# Page-10.net
KiCad netlist of a schematic drawn in Altium Designer
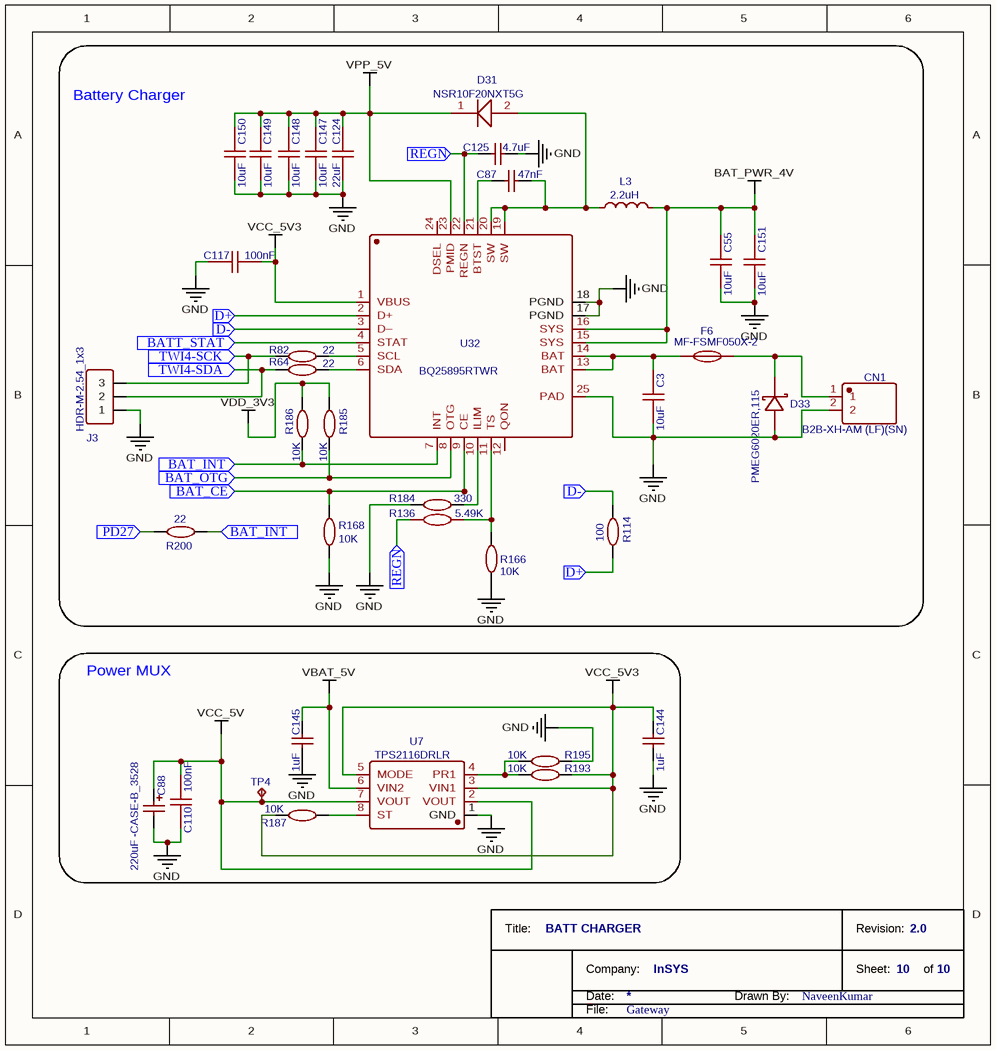
[diagram p0: Page-10.schdoc]

(export (version "E")
  (design (tool "Eeschema 10.0.6"))
  (components
    (comp (ref "*")
      (value "TitleBlock_1")
      (description "TitleBlock  No-2")
      (fields (field (name "DRAWN BY") "*"))
      (libsource (lib "GateWay_AllwinnerV2") (part "TitleBlock_1"))
    )
    (comp (ref "C3")
      (value "10uF")
      (footprint "GWAY_Capacitor_0805")
      (fields
        (field (name "MANUFACTURER") "SAMSUNG(三星)")
        (field (name "MANUFACTURER PART") "CL21B106KOQNNNE")
      )
      (libsource (lib "altium-import") (part "root_1_10uF_"))
    )
    (comp (ref "C55")
      (value "10uF")
      (footprint "GWAY_Capacitor_0805")
      (fields
        (field (name "MANUFACTURER") "SAMSUNG(三星)")
        (field (name "MANUFACTURER PART") "CL21B106KOQNNNE")
      )
      (libsource (lib "altium-import") (part "root_1_10uF_"))
    )
    (comp (ref "C87")
      (value "47nF")
      (footprint "GWAY_Capacitor_0603")
      (fields (field (name "MANUFACTURER PART") "CL10B473KB8NNNC") (field (name "MANUFACTURER") "SAMSUNG"))
      (libsource (lib "altium-import") (part "root_0_47nF_"))
    )
    (comp (ref "C88")
      (value "220uF -CASE-B_3528")
      (footprint "GWAY_CASE-B")
      (fields (field (name "MANUFACTURER") "PANASONIC") (field (name "MANUFACTURER PART") "6TPE220MAZB"))
      (libsource (lib "altium-import") (part "root_3_220uF -CASE-B_3528_"))
    )
    (comp (ref "C110")
      (value "100nF")
      (footprint "GWAY_Capacitor_0603")
      (fields (field (name "MANUFACTURER") "SAMSUNG") (field (name "MANUFACTURER PART") "CL10B104KB8NNNC"))
      (libsource (lib "altium-import") (part "root_3_100nF_"))
    )
    (comp (ref "C117")
      (value "100nF")
      (footprint "GWAY_Capacitor_0603")
      (fields (field (name "MANUFACTURER") "SAMSUNG") (field (name "MANUFACTURER PART") "CL10B104KB8NNNC"))
      (libsource (lib "altium-import") (part "root_0_100nF_"))
    )
    (comp (ref "C124")
      (value "22uF")
      (footprint "GWAY_Capacitor_0805")
      (fields
        (field (name "MANUFACTURER") "TAIYO YUDEN")
        (field (name "MANUFACTURER PART") "LMK212BJ226MG-T")
      )
      (libsource (lib "altium-import") (part "root_3_22uF_"))
    )
    (comp (ref "C125")
      (value "4.7uF")
      (footprint "GWAY_Capacitor_0603")
      (fields (field (name "MANUFACTURER PART") "CL10A475KQ8NNNC") (field (name "MANUFACTURER") "SAMSUNG"))
      (libsource (lib "altium-import") (part "root_2_4.7uF_"))
    )
    (comp (ref "C144")
      (value "1uF")
      (footprint "GWAY_Capacitor_0603")
      (fields
        (field (name "MANUFACTURER PART") "CL10B105KA8NNNC")
        (field (name "MANUFACTURER") "SAMSUNG(三星)")
      )
      (libsource (lib "altium-import") (part "root_3_1uF_"))
    )
    (comp (ref "C145")
      (value "1uF")
      (footprint "GWAY_Capacitor_0603")
      (fields
        (field (name "MANUFACTURER PART") "CL10B105KA8NNNC")
        (field (name "MANUFACTURER") "SAMSUNG(三星)")
      )
      (libsource (lib "altium-import") (part "root_3_1uF_"))
    )
    (comp (ref "C147")
      (value "10uF")
      (footprint "GWAY_Capacitor_0805")
      (fields
        (field (name "MANUFACTURER") "SAMSUNG(三星)")
        (field (name "MANUFACTURER PART") "CL21B106KOQNNNE")
      )
      (libsource (lib "altium-import") (part "root_1_10uF_"))
    )
    (comp (ref "C148")
      (value "10uF")
      (footprint "GWAY_Capacitor_0805")
      (fields
        (field (name "MANUFACTURER") "SAMSUNG(三星)")
        (field (name "MANUFACTURER PART") "CL21B106KOQNNNE")
      )
      (libsource (lib "altium-import") (part "root_1_10uF_"))
    )
    (comp (ref "C149")
      (value "10uF")
      (footprint "GWAY_Capacitor_0805")
      (fields
        (field (name "MANUFACTURER") "SAMSUNG(三星)")
        (field (name "MANUFACTURER PART") "CL21B106KOQNNNE")
      )
      (libsource (lib "altium-import") (part "root_1_10uF_"))
    )
    (comp (ref "C150")
      (value "10uF")
      (footprint "GWAY_Capacitor_0805")
      (fields
        (field (name "MANUFACTURER") "SAMSUNG(三星)")
        (field (name "MANUFACTURER PART") "CL21B106KOQNNNE")
      )
      (libsource (lib "altium-import") (part "root_1_10uF_"))
    )
    (comp (ref "C151")
      (value "10uF")
      (footprint "GWAY_Capacitor_0805")
      (fields
        (field (name "MANUFACTURER") "SAMSUNG(三星)")
        (field (name "MANUFACTURER PART") "CL21B106KOQNNNE")
      )
      (libsource (lib "altium-import") (part "root_1_10uF_"))
    )
    (comp (ref "CN1")
      (value "B2B-XH-AM (LF)(SN)")
      (footprint "GWAY_B2P-VH-LF-SN")
      (fields
        (field (name "MANUFACTURER") "JST")
        (field (name "MANUFACTURER PART") "B2B-XH-AM(LF)(SN)")
        (field (name "CONTRIBUTOR") "LCSC")
      )
      (libsource (lib "altium-import") (part "root_0_B2B-XH-AM (LF)(SN)_"))
    )
    (comp (ref "D31")
      (value "NSR10F20NXT5G")
      (footprint "GWAY_DSN2_0502")
      (libsource (lib "altium-import") (part "root_2_NSR10F20NXT5G_"))
    )
    (comp (ref "D33")
      (value "PMEG6020ER,115")
      (footprint "GWAY_SOD123F")
      (fields (field (name "MANUFACTURER") "Nexperia") (field (name "CONTRIBUTOR") "LCSC"))
      (libsource (lib "altium-import") (part "root_3_PMEG6020ER,115_"))
    )
    (comp (ref "F6")
      (value "MF-FSMF050X-2")
      (footprint "GWAY_FUSE0805")
      (fields (field (name "MANUFACTURER") "BOURNS") (field (name "CONTRIBUTOR") "LCSC"))
      (libsource (lib "altium-import") (part "root_0_MF-FSMF050X-2_"))
    )
    (comp (ref "J3")
      (value "HDR-M-2.54_1x3")
      (footprint "GWAY_3Way_Header_Conn")
      (fields (field (name "CONTRIBUTOR") "LCEDA_Lib"))
      (libsource (lib "altium-import") (part "root_2_HDR-M-2.54_1x3_"))
    )
    (comp (ref "L3")
      (value "2.2uH")
      (footprint "GWAY_INDUCTOR_6_5X6_5X3")
      (fields
        (field (name "MANUFACTURER") "VISHAY(威世)")
        (field (name "MANUFACTURER PART") "IHLP2525CZER2R2M01")
        (field (name "CONTRIBUTOR") "LCSC")
      )
      (libsource (lib "altium-import") (part "root_0_2.2uH_"))
    )
    (comp (ref "R64")
      (value "22")
      (footprint "GWAY_Resistor_0603")
      (fields (field (name "MANUFACTURER") "YAGEO") (field (name "MANUFACTURER PART") "RC0603FR-0722RL"))
      (libsource (lib "altium-import") (part "root_0_22_"))
    )
    (comp (ref "R82")
      (value "22")
      (footprint "GWAY_Resistor_0603")
      (fields (field (name "MANUFACTURER") "YAGEO") (field (name "MANUFACTURER PART") "RC0603FR-0722RL"))
      (libsource (lib "altium-import") (part "root_0_22_"))
    )
    (comp (ref "R114")
      (value "100")
      (footprint "GWAY_Resistor_0603")
      (fields (field (name "MANUFACTURER") "YAGEO") (field (name "MANUFACTURER PART") "RC0603FR-07100RL"))
      (libsource (lib "altium-import") (part "root_1_100_"))
    )
    (comp (ref "R136")
      (value "5.49K")
      (footprint "GWAY_Resistor_0603")
      (fields
        (field (name "MANUFACTURER") "YAGEO")
        (field (name "MANUFACTURER PART") "RC0603FR-075K49L")
        (field (name "CONTRIBUTOR") "LCSC")
      )
      (libsource (lib "altium-import") (part "root_0_5.49K_"))
    )
    (comp (ref "R166")
      (value "10K")
      (footprint "GWAY_Resistor_0603")
      (fields (field (name "MANUFACTURER") "YAGEO") (field (name "MANUFACTURER PART") "RC0603JR-0710KL"))
      (libsource (lib "altium-import") (part "root_3_10K_"))
    )
    (comp (ref "R168")
      (value "10K")
      (footprint "GWAY_Resistor_0603")
      (fields (field (name "MANUFACTURER") "YAGEO") (field (name "MANUFACTURER PART") "RC0603JR-0710KL"))
      (libsource (lib "altium-import") (part "root_1_10K_"))
    )
    (comp (ref "R184")
      (value "330")
      (footprint "GWAY_Resistor_0603")
      (fields (field (name "MANUFACTURER") "YAGEO") (field (name "MANUFACTURER PART") "RC0603FR-07330RL"))
      (libsource (lib "altium-import") (part "root_0_330_"))
    )
    (comp (ref "R185")
      (value "10K")
      (footprint "GWAY_Resistor_0603")
      (fields (field (name "MANUFACTURER") "YAGEO") (field (name "MANUFACTURER PART") "RC0603JR-0710KL"))
      (libsource (lib "altium-import") (part "root_3_10K_"))
    )
    (comp (ref "R186")
      (value "10K")
      (footprint "GWAY_Resistor_0603")
      (fields (field (name "MANUFACTURER") "YAGEO") (field (name "MANUFACTURER PART") "RC0603JR-0710KL"))
      (libsource (lib "altium-import") (part "root_3_10K_"))
    )
    (comp (ref "R187")
      (value "10K")
      (footprint "GWAY_Resistor_0603")
      (fields (field (name "MANUFACTURER") "YAGEO") (field (name "MANUFACTURER PART") "RC0603JR-0710KL"))
      (libsource (lib "altium-import") (part "root_2_10K_"))
    )
    (comp (ref "R193")
      (value "10K")
      (footprint "GWAY_Resistor_0603")
      (fields (field (name "MANUFACTURER") "YAGEO") (field (name "MANUFACTURER PART") "RC0603JR-0710KL"))
      (libsource (lib "altium-import") (part "root_2_10K_"))
    )
    (comp (ref "R195")
      (value "10K")
      (footprint "GWAY_Resistor_0603")
      (fields (field (name "MANUFACTURER") "YAGEO") (field (name "MANUFACTURER PART") "RC0603JR-0710KL"))
      (libsource (lib "altium-import") (part "root_2_10K_"))
    )
    (comp (ref "R200")
      (value "22")
      (footprint "GWAY_Resistor_0603")
      (fields (field (name "MANUFACTURER") "YAGEO") (field (name "MANUFACTURER PART") "RC0603FR-0722RL"))
      (libsource (lib "altium-import") (part "root_0_22_"))
    )
    (comp (ref "TP4")
      (value "TP-052-TJ")
      (footprint "GWAY_TESTPOINT1")
      (fields (field (name "MANUFACTURER PART") "?"))
      (libsource (lib "altium-import") (part "root_0_TP-052-TJ_"))
    )
    (comp (ref "U7")
      (value "TPS2116DRLR")
      (footprint "GWAY_SOT_583_8PIN")
      (fields (field (name "MANUFACTURER") "TI(德州仪器)") (field (name "CONTRIBUTOR") "lcsc"))
      (libsource (lib "altium-import") (part "root_2_TPS2116DRLR_"))
    )
    (comp (ref "U32")
      (value "BQ25895RTWR")
      (footprint "GWAY_QFN_24PIN_4X4X1-25N")
      (fields (field (name "MANUFACTURER") "TI") (field (name "CONTRIBUTOR") "LCSC"))
      (libsource (lib "altium-import") (part "root_0_BQ25895RTWR_"))
    )
  )
  (nets
    (net (code "1") (name "/BATT_STAT") (class "Default")
      (node (ref "U32") (pin "4") (pinfunction "STAT_4") (pintype "passive"))
    )
    (net (code "2") (name "/BAT_CE") (class "Default")
      (node (ref "R168") (pin "2") (pinfunction "2_2") (pintype "passive"))
      (node (ref "U32") (pin "9") (pinfunction "CE_9") (pintype "passive"))
    )
    (net (code "3") (name "/BAT_INT") (class "Default")
      (node (ref "R186") (pin "2") (pinfunction "2_2") (pintype "passive"))
      (node (ref "R200") (pin "2") (pinfunction "2_2") (pintype "passive"))
      (node (ref "U32") (pin "7") (pinfunction "INT_7") (pintype "passive"))
    )
    (net (code "4") (name "/BAT_OTG") (class "Default")
      (node (ref "R185") (pin "2") (pinfunction "2_2") (pintype "passive"))
      (node (ref "U32") (pin "8") (pinfunction "OTG_8") (pintype "passive"))
    )
    (net (code "5") (name "/D+") (class "Default")
      (node (ref "R114") (pin "1") (pinfunction "1_1") (pintype "passive"))
      (node (ref "U32") (pin "2") (pinfunction "D+_2") (pintype "passive"))
    )
    (net (code "6") (name "/D-") (class "Default")
      (node (ref "R114") (pin "2") (pinfunction "2_2") (pintype "passive"))
      (node (ref "U32") (pin "3") (pinfunction "D–_3") (pintype "passive"))
    )
    (net (code "7") (name "/PD27") (class "Default")
      (node (ref "R200") (pin "1") (pinfunction "1_1") (pintype "passive"))
    )
    (net (code "8") (name "/REGN") (class "Default")
      (node (ref "C125") (pin "2") (pinfunction "2_2") (pintype "passive"))
      (node (ref "R136") (pin "1") (pinfunction "1_1") (pintype "passive"))
      (node (ref "U32") (pin "22") (pinfunction "REGN_22") (pintype "passive"))
    )
    (net (code "9") (name "/TWI4-SCK") (class "Default")
      (node (ref "J3") (pin "3") (pinfunction "3_3") (pintype "passive"))
      (node (ref "R82") (pin "1") (pinfunction "1_1") (pintype "passive"))
    )
    (net (code "10") (name "/TWI4-SDA") (class "Default")
      (node (ref "J3") (pin "2") (pinfunction "2_2") (pintype "passive"))
      (node (ref "R64") (pin "1") (pinfunction "1_1") (pintype "passive"))
    )
    (net (code "11") (name "BAT_PWR_4V") (class "Default")
      (node (ref "C151") (pin "2") (pinfunction "2_2") (pintype "passive"))
      (node (ref "C55") (pin "2") (pinfunction "2_2") (pintype "passive"))
      (node (ref "L3") (pin "2") (pinfunction "2_2") (pintype "passive"))
      (node (ref "U32") (pin "15") (pinfunction "SYS_15") (pintype "passive"))
      (node (ref "U32") (pin "16") (pinfunction "SYS_16") (pintype "passive"))
    )
    (net (code "12") (name "GND") (class "Default")
      (node (ref "C110") (pin "2") (pinfunction "2_2") (pintype "passive"))
      (node (ref "C117") (pin "1") (pinfunction "1_1") (pintype "passive"))
      (node (ref "C124") (pin "2") (pinfunction "2_2") (pintype "passive"))
      (node (ref "C125") (pin "1") (pinfunction "1_1") (pintype "passive"))
      (node (ref "C144") (pin "2") (pinfunction "2_2") (pintype "passive"))
      (node (ref "C145") (pin "2") (pinfunction "2_2") (pintype "passive"))
      (node (ref "C147") (pin "1") (pinfunction "1_1") (pintype "passive"))
      (node (ref "C148") (pin "1") (pinfunction "1_1") (pintype "passive"))
      (node (ref "C149") (pin "1") (pinfunction "1_1") (pintype "passive"))
      (node (ref "C150") (pin "1") (pinfunction "1_1") (pintype "passive"))
      (node (ref "C151") (pin "1") (pinfunction "1_1") (pintype "passive"))
      (node (ref "C3") (pin "1") (pinfunction "1_1") (pintype "passive"))
      (node (ref "C55") (pin "1") (pinfunction "1_1") (pintype "passive"))
      (node (ref "C88") (pin "2") (pinfunction "2_2") (pintype "passive"))
      (node (ref "CN1") (pin "2") (pinfunction "2_2") (pintype "passive"))
      (node (ref "D33") (pin "2") (pinfunction "A_2") (pintype "passive"))
      (node (ref "J3") (pin "1") (pinfunction "1_1") (pintype "passive"))
      (node (ref "R166") (pin "2") (pinfunction "2_2") (pintype "passive"))
      (node (ref "R168") (pin "1") (pinfunction "1_1") (pintype "passive"))
      (node (ref "R184") (pin "1") (pinfunction "1_1") (pintype "passive"))
      (node (ref "R195") (pin "1") (pinfunction "1_1") (pintype "passive"))
      (node (ref "U32") (pin "17") (pinfunction "PGND_17") (pintype "passive"))
      (node (ref "U32") (pin "18") (pinfunction "PGND_18") (pintype "passive"))
      (node (ref "U32") (pin "25") (pinfunction "PAD_25") (pintype "passive"))
      (node (ref "U7") (pin "1") (pinfunction "GND_1") (pintype "passive"))
    )
    (net (code "13") (name "Net-(C3-Pad2)") (class "Default")
      (node (ref "C3") (pin "2") (pinfunction "2_2") (pintype "passive"))
      (node (ref "F6") (pin "1") (pinfunction "1_1") (pintype "passive"))
      (node (ref "U32") (pin "13") (pinfunction "BAT_13") (pintype "passive"))
      (node (ref "U32") (pin "14") (pinfunction "BAT_14") (pintype "passive"))
    )
    (net (code "14") (name "Net-(D31-A)") (class "Default")
      (node (ref "C87") (pin "2") (pinfunction "2_2") (pintype "passive"))
      (node (ref "D31") (pin "2") (pinfunction "A_2") (pintype "passive"))
      (node (ref "L3") (pin "1") (pinfunction "1_1") (pintype "passive"))
      (node (ref "U32") (pin "19") (pinfunction "SW_19") (pintype "passive"))
      (node (ref "U32") (pin "20") (pinfunction "SW_20") (pintype "passive"))
    )
    (net (code "15") (name "Net-(D33-C)") (class "Default")
      (node (ref "CN1") (pin "1") (pinfunction "1_1") (pintype "passive"))
      (node (ref "D33") (pin "1") (pinfunction "C_1") (pintype "passive"))
      (node (ref "F6") (pin "2") (pinfunction "2_2") (pintype "passive"))
    )
    (net (code "16") (name "Net-(U7-PR1)") (class "Default")
      (node (ref "R193") (pin "2") (pinfunction "2_2") (pintype "passive"))
      (node (ref "R195") (pin "2") (pinfunction "2_2") (pintype "passive"))
      (node (ref "U7") (pin "4") (pinfunction "PR1_4") (pintype "passive"))
    )
    (net (code "17") (name "Net-(U7-ST)") (class "Default")
      (node (ref "R187") (pin "1") (pinfunction "1_1") (pintype "passive"))
      (node (ref "U7") (pin "8") (pinfunction "ST_8") (pintype "passive"))
    )
    (net (code "18") (name "Net-(U32-BTST)") (class "Default")
      (node (ref "C87") (pin "1") (pinfunction "1_1") (pintype "passive"))
      (node (ref "U32") (pin "21") (pinfunction "BTST_21") (pintype "passive"))
    )
    (net (code "19") (name "Net-(U32-ILIM)") (class "Default")
      (node (ref "R184") (pin "2") (pinfunction "2_2") (pintype "passive"))
      (node (ref "U32") (pin "10") (pinfunction "ILIM_10") (pintype "passive"))
    )
    (net (code "20") (name "Net-(U32-SCL)") (class "Default")
      (node (ref "R82") (pin "2") (pinfunction "2_2") (pintype "passive"))
      (node (ref "U32") (pin "5") (pinfunction "SCL_5") (pintype "passive"))
    )
    (net (code "21") (name "Net-(U32-SDA)") (class "Default")
      (node (ref "R64") (pin "2") (pinfunction "2_2") (pintype "passive"))
      (node (ref "U32") (pin "6") (pinfunction "SDA_6") (pintype "passive"))
    )
    (net (code "22") (name "Net-(U32-TS)") (class "Default")
      (node (ref "R136") (pin "2") (pinfunction "2_2") (pintype "passive"))
      (node (ref "R166") (pin "1") (pinfunction "1_1") (pintype "passive"))
      (node (ref "U32") (pin "11") (pinfunction "TS_11") (pintype "passive"))
    )
    (net (code "23") (name "VBAT_5V") (class "Default")
      (node (ref "C145") (pin "1") (pinfunction "1_1") (pintype "passive"))
      (node (ref "U7") (pin "6") (pinfunction "VIN2_6") (pintype "passive"))
    )
    (net (code "24") (name "VCC_5V") (class "Default")
      (node (ref "C110") (pin "1") (pinfunction "1_1") (pintype "passive"))
      (node (ref "C88") (pin "1") (pinfunction "1_1") (pintype "passive"))
      (node (ref "TP4") (pin "1") (pinfunction "1_1") (pintype "passive"))
      (node (ref "U7") (pin "2") (pinfunction "VOUT_2") (pintype "passive"))
      (node (ref "U7") (pin "7") (pinfunction "VOUT_7") (pintype "passive"))
    )
    (net (code "25") (name "VCC_5V3") (class "Default")
      (node (ref "C117") (pin "2") (pinfunction "2_2") (pintype "passive"))
      (node (ref "C144") (pin "1") (pinfunction "1_1") (pintype "passive"))
      (node (ref "R187") (pin "2") (pinfunction "2_2") (pintype "passive"))
      (node (ref "R193") (pin "1") (pinfunction "1_1") (pintype "passive"))
      (node (ref "U32") (pin "1") (pinfunction "VBUS_1") (pintype "passive"))
      (node (ref "U7") (pin "3") (pinfunction "VIN1_3") (pintype "passive"))
      (node (ref "U7") (pin "5") (pinfunction "MODE_5") (pintype "passive"))
    )
    (net (code "26") (name "VDD_3V3") (class "Default")
      (node (ref "R185") (pin "1") (pinfunction "1_1") (pintype "passive"))
      (node (ref "R186") (pin "1") (pinfunction "1_1") (pintype "passive"))
    )
    (net (code "27") (name "VPP_5V") (class "Default")
      (node (ref "C124") (pin "1") (pinfunction "1_1") (pintype "passive"))
      (node (ref "C147") (pin "2") (pinfunction "2_2") (pintype "passive"))
      (node (ref "C148") (pin "2") (pinfunction "2_2") (pintype "passive"))
      (node (ref "C149") (pin "2") (pinfunction "2_2") (pintype "passive"))
      (node (ref "C150") (pin "2") (pinfunction "2_2") (pintype "passive"))
      (node (ref "D31") (pin "1") (pinfunction "K_1") (pintype "passive"))
      (node (ref "U32") (pin "23") (pinfunction "PMID_23") (pintype "passive"))
    )
    (net (code "28") (name "unconnected-(U32-DSEL-Pad24)") (class "Default")
      (node (ref "U32") (pin "24") (pinfunction "DSEL_24") (pintype "passive"))
    )
    (net (code "29") (name "unconnected-(U32-QON-Pad12)") (class "Default")
      (node (ref "U32") (pin "12") (pinfunction "QON_12") (pintype "passive"))
    )
  )
)
